# High_Current_H-Bridge.net
KiCad netlist of a schematic drawn in Altium Designer
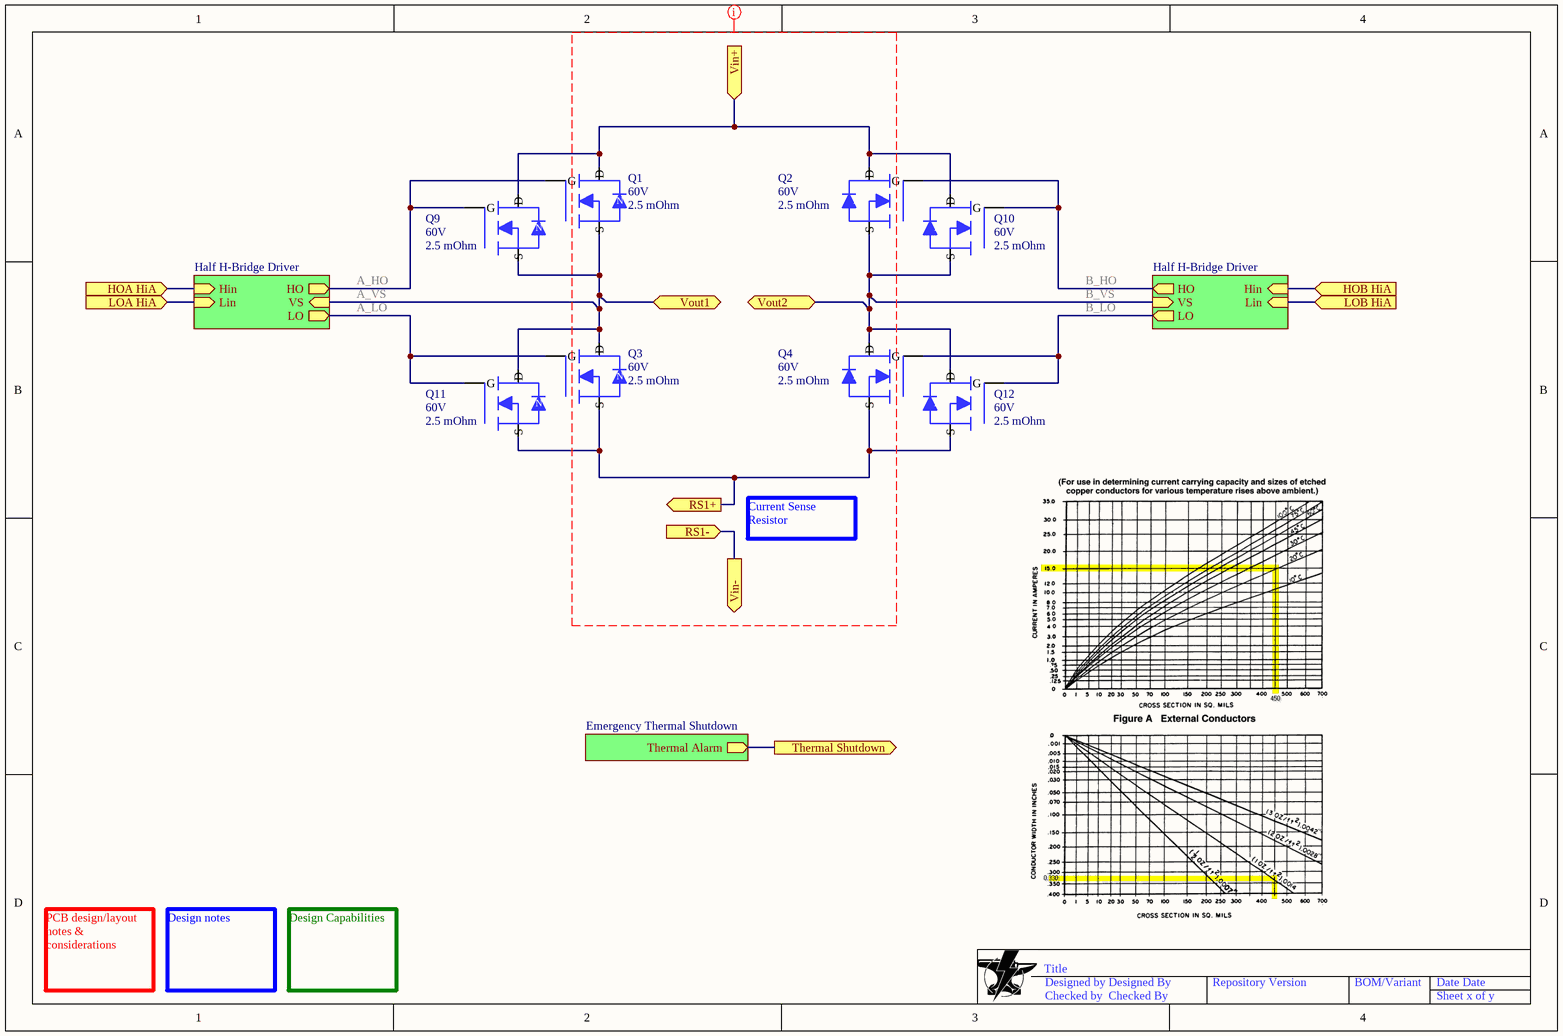
[diagram p0: High Current H-Bridge.SchDoc]

(export (version "E")
  (design (tool "Eeschema 10.0.6"))
  (components
    (comp (ref "Q1")
      (value "N-MOSFET")
      (footprint "DPAK")
      (fields
        (field (name "MANUFACTURER") "Infineon Technologies")
        (field (name "MANUFACTURER PART NUMBER") "IPD025N06N")
        (field (name "DRAIN TO SOURCE VOLTAGE (VDSS)") "60V")
        (field (name "RDS ON (MAX) @ ID, VGS") "2.5 mOhm")
      )
      (libsource (lib "Local Library") (part "N-MOSFET 2.5mR 60V"))
    )
    (comp (ref "Q2")
      (value "N-MOSFET")
      (footprint "DPAK")
      (fields
        (field (name "MANUFACTURER") "Infineon Technologies")
        (field (name "MANUFACTURER PART NUMBER") "IPD025N06N")
        (field (name "DRAIN TO SOURCE VOLTAGE (VDSS)") "60V")
        (field (name "RDS ON (MAX) @ ID, VGS") "2.5 mOhm")
      )
      (libsource (lib "Local Library") (part "N-MOSFET 2.5mR 60V"))
    )
    (comp (ref "Q3")
      (value "N-MOSFET")
      (footprint "DPAK")
      (fields
        (field (name "MANUFACTURER") "Infineon Technologies")
        (field (name "MANUFACTURER PART NUMBER") "IPD025N06N")
        (field (name "DRAIN TO SOURCE VOLTAGE (VDSS)") "60V")
        (field (name "RDS ON (MAX) @ ID, VGS") "2.5 mOhm")
      )
      (libsource (lib "Local Library") (part "N-MOSFET 2.5mR 60V"))
    )
    (comp (ref "Q4")
      (value "N-MOSFET")
      (footprint "DPAK")
      (fields
        (field (name "MANUFACTURER") "Infineon Technologies")
        (field (name "MANUFACTURER PART NUMBER") "IPD025N06N")
        (field (name "DRAIN TO SOURCE VOLTAGE (VDSS)") "60V")
        (field (name "RDS ON (MAX) @ ID, VGS") "2.5 mOhm")
      )
      (libsource (lib "Local Library") (part "N-MOSFET 2.5mR 60V"))
    )
    (comp (ref "Q9")
      (value "N-MOSFET")
      (footprint "DPAK")
      (fields
        (field (name "MANUFACTURER") "Infineon Technologies")
        (field (name "MANUFACTURER PART NUMBER") "IPD025N06N")
        (field (name "DRAIN TO SOURCE VOLTAGE (VDSS)") "60V")
        (field (name "RDS ON (MAX) @ ID, VGS") "2.5 mOhm")
      )
      (libsource (lib "Local Library") (part "N-MOSFET 2.5mR 60V"))
    )
    (comp (ref "Q10")
      (value "N-MOSFET")
      (footprint "DPAK")
      (fields
        (field (name "MANUFACTURER") "Infineon Technologies")
        (field (name "MANUFACTURER PART NUMBER") "IPD025N06N")
        (field (name "DRAIN TO SOURCE VOLTAGE (VDSS)") "60V")
        (field (name "RDS ON (MAX) @ ID, VGS") "2.5 mOhm")
      )
      (libsource (lib "Local Library") (part "N-MOSFET 2.5mR 60V"))
    )
    (comp (ref "Q11")
      (value "N-MOSFET")
      (footprint "DPAK")
      (fields
        (field (name "MANUFACTURER") "Infineon Technologies")
        (field (name "MANUFACTURER PART NUMBER") "IPD025N06N")
        (field (name "DRAIN TO SOURCE VOLTAGE (VDSS)") "60V")
        (field (name "RDS ON (MAX) @ ID, VGS") "2.5 mOhm")
      )
      (libsource (lib "Local Library") (part "N-MOSFET 2.5mR 60V"))
    )
    (comp (ref "Q12")
      (value "N-MOSFET")
      (footprint "DPAK")
      (fields
        (field (name "MANUFACTURER") "Infineon Technologies")
        (field (name "MANUFACTURER PART NUMBER") "IPD025N06N")
        (field (name "DRAIN TO SOURCE VOLTAGE (VDSS)") "60V")
        (field (name "RDS ON (MAX) @ ID, VGS") "2.5 mOhm")
      )
      (libsource (lib "Local Library") (part "N-MOSFET 2.5mR 60V"))
    )
  )
  (nets
    (net (code "1") (name "/A_HO") (class "Default")
      (node (ref "Q1") (pin "1") (pinfunction "G_1") (pintype "passive"))
      (node (ref "Q9") (pin "1") (pinfunction "G_1") (pintype "passive"))
    )
    (net (code "2") (name "/A_LO") (class "Default")
      (node (ref "Q11") (pin "1") (pinfunction "G_1") (pintype "passive"))
      (node (ref "Q3") (pin "1") (pinfunction "G_1") (pintype "passive"))
    )
    (net (code "3") (name "/A_VS") (class "Default")
      (node (ref "Q1") (pin "3") (pinfunction "S_3") (pintype "passive"))
      (node (ref "Q11") (pin "2") (pinfunction "D_2") (pintype "passive"))
      (node (ref "Q3") (pin "2") (pinfunction "D_2") (pintype "passive"))
      (node (ref "Q9") (pin "3") (pinfunction "S_3") (pintype "passive"))
    )
    (net (code "4") (name "/B_HO") (class "Default")
      (node (ref "Q10") (pin "1") (pinfunction "G_1") (pintype "passive"))
      (node (ref "Q2") (pin "1") (pinfunction "G_1") (pintype "passive"))
    )
    (net (code "5") (name "/B_LO") (class "Default")
      (node (ref "Q12") (pin "1") (pinfunction "G_1") (pintype "passive"))
      (node (ref "Q4") (pin "1") (pinfunction "G_1") (pintype "passive"))
    )
    (net (code "6") (name "/B_VS") (class "Default")
      (node (ref "Q10") (pin "3") (pinfunction "S_3") (pintype "passive"))
      (node (ref "Q12") (pin "2") (pinfunction "D_2") (pintype "passive"))
      (node (ref "Q2") (pin "3") (pinfunction "S_3") (pintype "passive"))
      (node (ref "Q4") (pin "2") (pinfunction "D_2") (pintype "passive"))
    )
    (net (code "11") (name "/RS1+") (class "Default")
      (node (ref "Q11") (pin "3") (pinfunction "S_3") (pintype "passive"))
      (node (ref "Q12") (pin "3") (pinfunction "S_3") (pintype "passive"))
      (node (ref "Q3") (pin "3") (pinfunction "S_3") (pintype "passive"))
      (node (ref "Q4") (pin "3") (pinfunction "S_3") (pintype "passive"))
    )
    (net (code "14") (name "/Vin+") (class "Default")
      (node (ref "Q1") (pin "2") (pinfunction "D_2") (pintype "passive"))
      (node (ref "Q10") (pin "2") (pinfunction "D_2") (pintype "passive"))
      (node (ref "Q2") (pin "2") (pinfunction "D_2") (pintype "passive"))
      (node (ref "Q9") (pin "2") (pinfunction "D_2") (pintype "passive"))
    )
  )
)
